# AD7685_v1.net
KiCad netlist of a schematic drawn in EAGLE
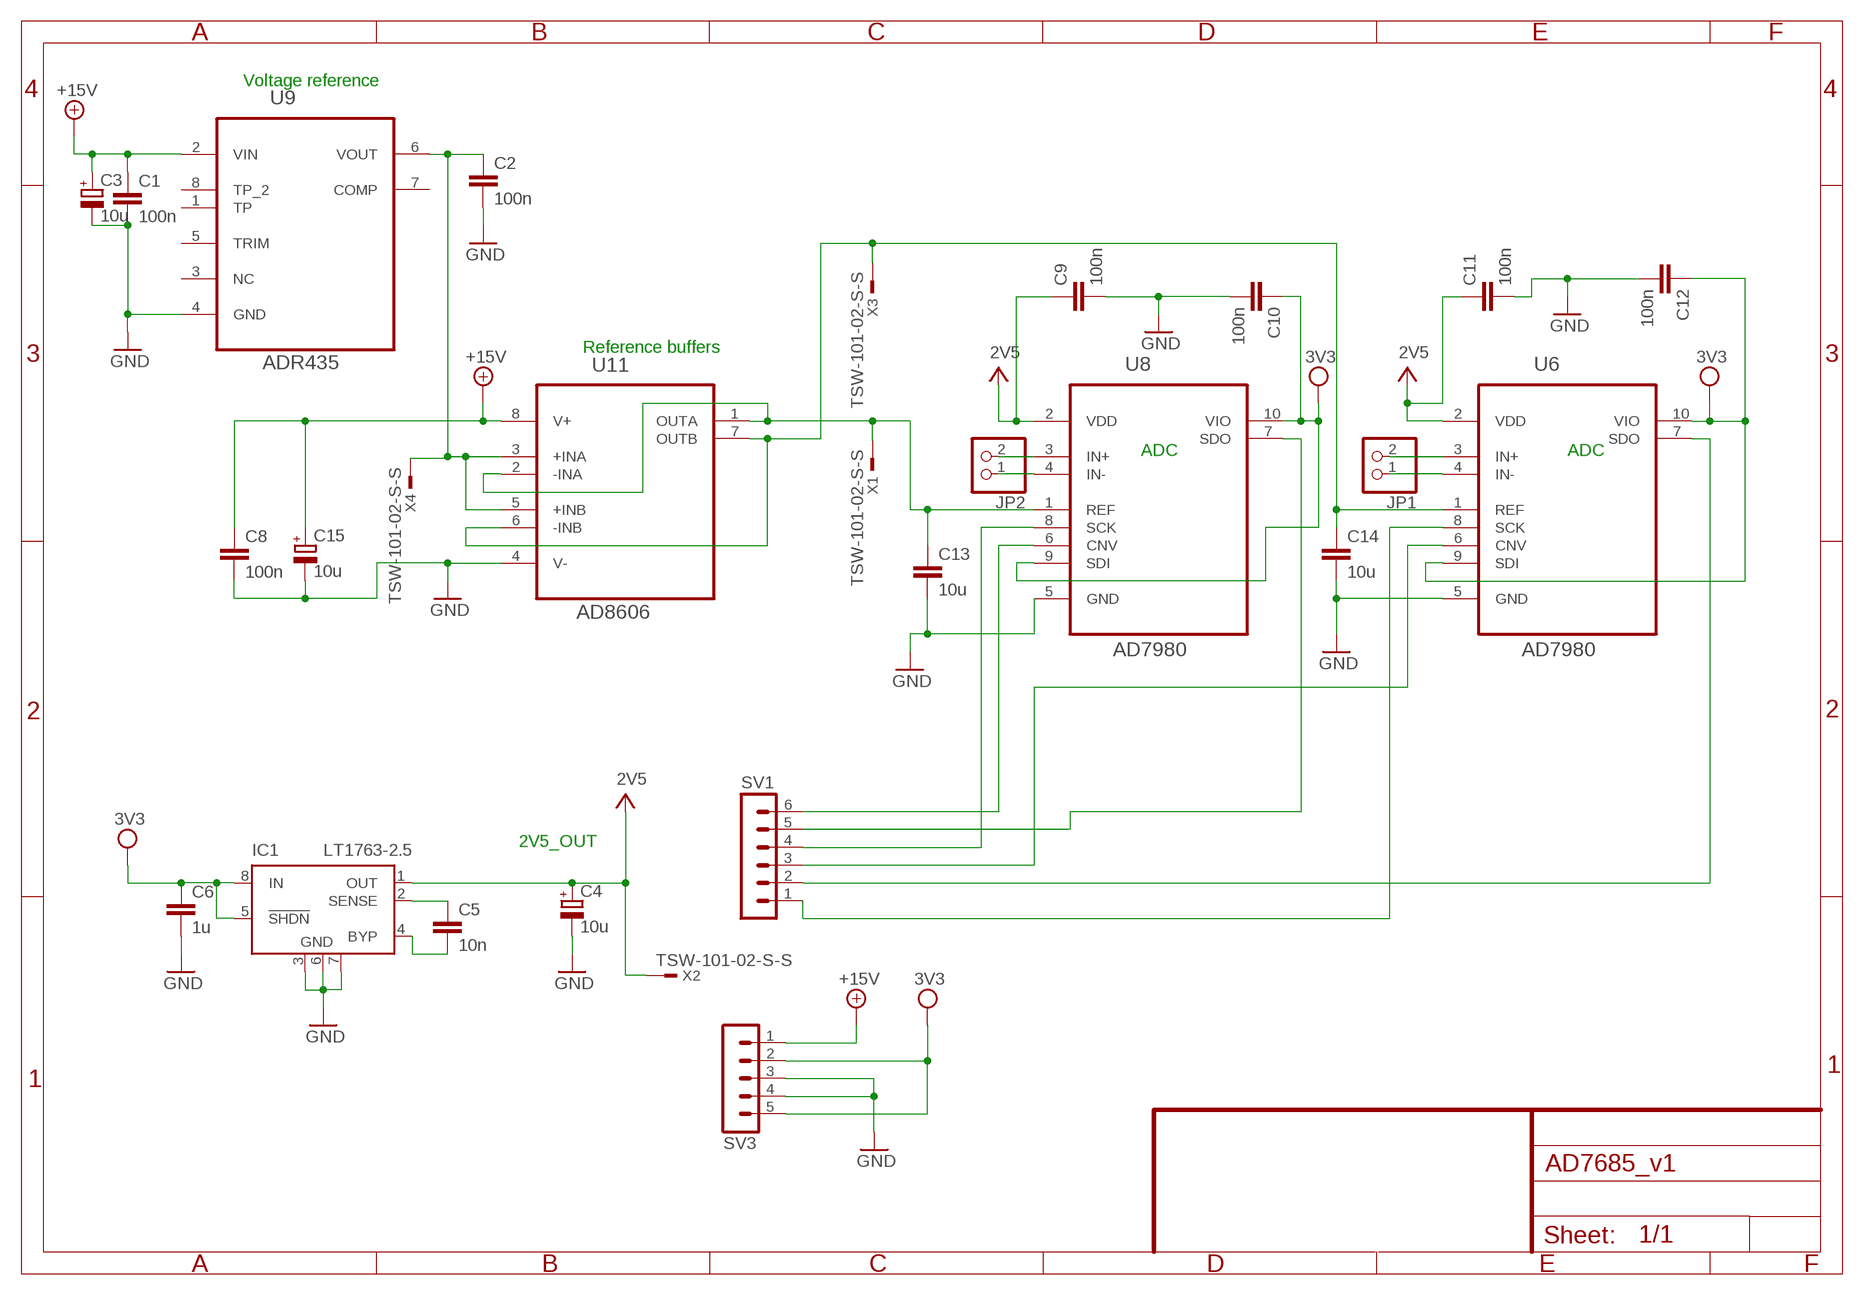
[diagram p0: schematic, sheet 1]

(export (version "E")
  (design (tool "Eeschema 10.0.6"))
  (components
    (comp (ref "C1")
      (value "100n")
      (footprint "eagle-import:C0603K")
      (libsource (lib "eagle-import") (part "C-EUC0603K"))
    )
    (comp (ref "C2")
      (value "100n")
      (footprint "eagle-import:C0603K")
      (libsource (lib "eagle-import") (part "C-EUC0603K"))
    )
    (comp (ref "C3")
      (value "10u")
      (footprint "eagle-import:SMC_A")
      (libsource (lib "eagle-import") (part "CPOL-EUSMCA"))
    )
    (comp (ref "C4")
      (value "10u")
      (footprint "eagle-import:SMC_A")
      (libsource (lib "eagle-import") (part "CPOL-EUSMCA"))
    )
    (comp (ref "C5")
      (value "10n")
      (footprint "eagle-import:C0603K")
      (libsource (lib "eagle-import") (part "C-EUC0603K"))
    )
    (comp (ref "C6")
      (value "1u")
      (footprint "eagle-import:C0603K")
      (libsource (lib "eagle-import") (part "C-EUC0603K"))
    )
    (comp (ref "C8")
      (value "100n")
      (footprint "eagle-import:C0603K")
      (libsource (lib "eagle-import") (part "C-EUC0603K"))
    )
    (comp (ref "C9")
      (value "100n")
      (footprint "eagle-import:C0603K")
      (libsource (lib "eagle-import") (part "C-EUC0603K"))
    )
    (comp (ref "C10")
      (value "100n")
      (footprint "eagle-import:C0603K")
      (libsource (lib "eagle-import") (part "C-EUC0603K"))
    )
    (comp (ref "C11")
      (value "100n")
      (footprint "eagle-import:C0603K")
      (libsource (lib "eagle-import") (part "C-EUC0603K"))
    )
    (comp (ref "C12")
      (value "100n")
      (footprint "eagle-import:C0603K")
      (libsource (lib "eagle-import") (part "C-EUC0603K"))
    )
    (comp (ref "C13")
      (value "10u")
      (footprint "eagle-import:C0603K")
      (libsource (lib "eagle-import") (part "C-EUC0603K"))
    )
    (comp (ref "C14")
      (value "10u")
      (footprint "eagle-import:C0603K")
      (libsource (lib "eagle-import") (part "C-EUC0603K"))
    )
    (comp (ref "C15")
      (value "10u")
      (footprint "eagle-import:SMC_A")
      (libsource (lib "eagle-import") (part "CPOL-EUSMCA"))
    )
    (comp (ref "IC1")
      (value "LT1763-2.5")
      (footprint "eagle-import:SOIC8")
      (fields (field (name "MPN") "LT1763CS8-2.5"))
      (libsource (lib "eagle-import") (part "LT1763CS8-2.5"))
    )
    (comp (ref "JP1")
      (value "PINHD-1X2")
      (footprint "eagle-import:1X02")
      (libsource (lib "eagle-import") (part "PINHD-1X2"))
    )
    (comp (ref "JP2")
      (value "PINHD-1X2")
      (footprint "eagle-import:1X02")
      (libsource (lib "eagle-import") (part "PINHD-1X2"))
    )
    (comp (ref "SV1")
      (value "MA06-1")
      (footprint "eagle-import:MA06-1")
      (libsource (lib "eagle-import") (part "MA06-1"))
    )
    (comp (ref "SV3")
      (value "MA05-1")
      (footprint "eagle-import:MA05-1")
      (libsource (lib "eagle-import") (part "MA05-1"))
    )
    (comp (ref "U6")
      (value "AD7980")
      (footprint "eagle-import:SOP50P490X110-10N")
      (fields (field (name "MPN") "AD7980BRMZ"))
      (libsource (lib "eagle-import") (part "AD7980BRMZ"))
    )
    (comp (ref "U8")
      (value "AD7980")
      (footprint "eagle-import:SOP50P490X110-10N")
      (fields (field (name "MPN") "AD7980BRMZ"))
      (libsource (lib "eagle-import") (part "AD7980BRMZ"))
    )
    (comp (ref "U9")
      (value "ADR435")
      (footprint "eagle-import:SOP65P490X110-8N")
      (fields (field (name "MPN") "ADR435ARMZ"))
      (libsource (lib "eagle-import") (part "ADR435ARMZ"))
    )
    (comp (ref "U11")
      (value "AD8606")
      (footprint "eagle-import:SOP65P490X110-8N")
      (fields (field (name "MPN") "AD8606ARMZ-R7"))
      (libsource (lib "eagle-import") (part "AD8606ARMZ-R7"))
    )
    (comp (ref "X1")
      (value "TSW-101-02-S-S")
      (footprint "eagle-import:TSW-101-02-S-S")
      (libsource (lib "eagle-import") (part "TSW-101-02-S-S"))
    )
    (comp (ref "X2")
      (value "TSW-101-02-S-S")
      (footprint "eagle-import:TSW-101-02-S-S")
      (libsource (lib "eagle-import") (part "TSW-101-02-S-S"))
    )
    (comp (ref "X3")
      (value "TSW-101-02-S-S")
      (footprint "eagle-import:TSW-101-02-S-S")
      (libsource (lib "eagle-import") (part "TSW-101-02-S-S"))
    )
    (comp (ref "X4")
      (value "TSW-101-02-S-S")
      (footprint "eagle-import:TSW-101-02-S-S")
      (libsource (lib "eagle-import") (part "TSW-101-02-S-S"))
    )
  )
  (nets
    (net (code "1") (name "+15V") (class "Default")
      (node (ref "C1") (pin "1") (pinfunction "1_1") (pintype "passive"))
      (node (ref "C15") (pin "+") (pinfunction "+_+") (pintype "passive"))
      (node (ref "C3") (pin "+") (pinfunction "+_+") (pintype "passive"))
      (node (ref "C8") (pin "1") (pinfunction "1_1") (pintype "passive"))
      (node (ref "SV3") (pin "1") (pinfunction "1_1") (pintype "passive"))
      (node (ref "U11") (pin "8") (pinfunction "V+_8") (pintype "power_in"))
      (node (ref "U9") (pin "2") (pinfunction "VIN_2") (pintype "power_in"))
    )
    (net (code "2") (name "/COMP") (class "Default")
      (node (ref "U9") (pin "7") (pinfunction "COMP_7") (pintype "power_in"))
    )
    (net (code "3") (name "2V5") (class "Default")
      (node (ref "C11") (pin "1") (pinfunction "1_1") (pintype "passive"))
      (node (ref "C4") (pin "+") (pinfunction "+_+") (pintype "passive"))
      (node (ref "C9") (pin "1") (pinfunction "1_1") (pintype "passive"))
      (node (ref "IC1") (pin "1") (pinfunction "OUT_1") (pintype "passive"))
      (node (ref "U6") (pin "2") (pinfunction "VDD_2") (pintype "power_in"))
      (node (ref "U8") (pin "2") (pinfunction "VDD_2") (pintype "power_in"))
      (node (ref "X2") (pin "1") (pinfunction "1_1") (pintype "passive"))
    )
    (net (code "4") (name "3V3") (class "Default")
      (node (ref "C10") (pin "1") (pinfunction "1_1") (pintype "passive"))
      (node (ref "C12") (pin "1") (pinfunction "1_1") (pintype "passive"))
      (node (ref "C6") (pin "1") (pinfunction "1_1") (pintype "passive"))
      (node (ref "IC1") (pin "5") (pinfunction "~{SHDN}_5") (pintype "input"))
      (node (ref "IC1") (pin "8") (pinfunction "IN_8") (pintype "input"))
      (node (ref "SV3") (pin "2") (pinfunction "2_2") (pintype "passive"))
      (node (ref "SV3") (pin "5") (pinfunction "5_5") (pintype "passive"))
      (node (ref "U6") (pin "10") (pinfunction "VIO_10") (pintype "bidirectional"))
      (node (ref "U6") (pin "9") (pinfunction "SDI_9") (pintype "input"))
      (node (ref "U8") (pin "10") (pinfunction "VIO_10") (pintype "bidirectional"))
      (node (ref "U8") (pin "9") (pinfunction "SDI_9") (pintype "input"))
    )
    (net (code "5") (name "GND") (class "Default")
      (node (ref "C1") (pin "2") (pinfunction "2_2") (pintype "passive"))
      (node (ref "C10") (pin "2") (pinfunction "2_2") (pintype "passive"))
      (node (ref "C11") (pin "2") (pinfunction "2_2") (pintype "passive"))
      (node (ref "C12") (pin "2") (pinfunction "2_2") (pintype "passive"))
      (node (ref "C13") (pin "2") (pinfunction "2_2") (pintype "passive"))
      (node (ref "C14") (pin "2") (pinfunction "2_2") (pintype "passive"))
      (node (ref "C15") (pin "-") (pinfunction "-_-") (pintype "passive"))
      (node (ref "C2") (pin "2") (pinfunction "2_2") (pintype "passive"))
      (node (ref "C3") (pin "-") (pinfunction "-_-") (pintype "passive"))
      (node (ref "C4") (pin "-") (pinfunction "-_-") (pintype "passive"))
      (node (ref "C6") (pin "2") (pinfunction "2_2") (pintype "passive"))
      (node (ref "C8") (pin "2") (pinfunction "2_2") (pintype "passive"))
      (node (ref "C9") (pin "2") (pinfunction "2_2") (pintype "passive"))
      (node (ref "IC1") (pin "3") (pinfunction "GND_3") (pintype "power_in"))
      (node (ref "IC1") (pin "6") (pinfunction "GND_6") (pintype "power_in"))
      (node (ref "IC1") (pin "7") (pinfunction "GND_7") (pintype "power_in"))
      (node (ref "SV3") (pin "3") (pinfunction "3_3") (pintype "passive"))
      (node (ref "SV3") (pin "4") (pinfunction "4_4") (pintype "passive"))
      (node (ref "U11") (pin "4") (pinfunction "V-_4") (pintype "power_in"))
      (node (ref "U6") (pin "5") (pinfunction "GND_5") (pintype "passive"))
      (node (ref "U8") (pin "5") (pinfunction "GND_5") (pintype "passive"))
      (node (ref "U9") (pin "4") (pinfunction "GND_4") (pintype "passive"))
    )
    (net (code "6") (name "Net-(IC1-BYP)") (class "Default")
      (node (ref "C5") (pin "2") (pinfunction "2_2") (pintype "passive"))
      (node (ref "IC1") (pin "4") (pinfunction "BYP_4") (pintype "input"))
    )
    (net (code "7") (name "Net-(IC1-SENSE)") (class "Default")
      (node (ref "C5") (pin "1") (pinfunction "1_1") (pintype "passive"))
      (node (ref "IC1") (pin "2") (pinfunction "SENSE_2") (pintype "input"))
    )
    (net (code "8") (name "Net-(U6-CNV)") (class "Default")
      (node (ref "SV1") (pin "3") (pinfunction "3_3") (pintype "passive"))
      (node (ref "U6") (pin "6") (pinfunction "CNV_6") (pintype "input"))
    )
    (net (code "9") (name "Net-(U6-IN+)") (class "Default")
      (node (ref "JP1") (pin "2") (pinfunction "2_2") (pintype "passive"))
      (node (ref "U6") (pin "3") (pinfunction "IN+_3") (pintype "input"))
    )
    (net (code "10") (name "Net-(U6-IN-)") (class "Default")
      (node (ref "JP1") (pin "1") (pinfunction "1_1") (pintype "passive"))
      (node (ref "U6") (pin "4") (pinfunction "IN-_4") (pintype "input"))
    )
    (net (code "11") (name "Net-(U6-SCK)") (class "Default")
      (node (ref "SV1") (pin "1") (pinfunction "1_1") (pintype "passive"))
      (node (ref "U6") (pin "8") (pinfunction "SCK_8") (pintype "input"))
    )
    (net (code "12") (name "Net-(U6-SDO)") (class "Default")
      (node (ref "SV1") (pin "2") (pinfunction "2_2") (pintype "passive"))
      (node (ref "U6") (pin "7") (pinfunction "SDO_7") (pintype "bidirectional"))
    )
    (net (code "13") (name "Net-(U8-CNV)") (class "Default")
      (node (ref "SV1") (pin "6") (pinfunction "6_6") (pintype "passive"))
      (node (ref "U8") (pin "6") (pinfunction "CNV_6") (pintype "input"))
    )
    (net (code "14") (name "Net-(U8-IN+)") (class "Default")
      (node (ref "JP2") (pin "2") (pinfunction "2_2") (pintype "passive"))
      (node (ref "U8") (pin "3") (pinfunction "IN+_3") (pintype "input"))
    )
    (net (code "15") (name "Net-(U8-IN-)") (class "Default")
      (node (ref "JP2") (pin "1") (pinfunction "1_1") (pintype "passive"))
      (node (ref "U8") (pin "4") (pinfunction "IN-_4") (pintype "input"))
    )
    (net (code "16") (name "Net-(U8-SCK)") (class "Default")
      (node (ref "SV1") (pin "4") (pinfunction "4_4") (pintype "passive"))
      (node (ref "U8") (pin "8") (pinfunction "SCK_8") (pintype "input"))
    )
    (net (code "17") (name "Net-(U8-SDO)") (class "Default")
      (node (ref "SV1") (pin "5") (pinfunction "5_5") (pintype "passive"))
      (node (ref "U8") (pin "7") (pinfunction "SDO_7") (pintype "bidirectional"))
    )
    (net (code "18") (name "Net-(U11-+INA)") (class "Default")
      (node (ref "C2") (pin "1") (pinfunction "1_1") (pintype "passive"))
      (node (ref "U11") (pin "3") (pinfunction "+INA_3") (pintype "input"))
      (node (ref "U11") (pin "5") (pinfunction "+INB_5") (pintype "input"))
      (node (ref "U9") (pin "6") (pinfunction "VOUT_6") (pintype "output"))
      (node (ref "X4") (pin "1") (pinfunction "1_1") (pintype "passive"))
    )
    (net (code "19") (name "Net-(U11--INA)") (class "Default")
      (node (ref "C13") (pin "1") (pinfunction "1_1") (pintype "passive"))
      (node (ref "U11") (pin "1") (pinfunction "OUTA_1") (pintype "output"))
      (node (ref "U11") (pin "2") (pinfunction "-INA_2") (pintype "input"))
      (node (ref "U8") (pin "1") (pinfunction "REF_1") (pintype "input"))
      (node (ref "X1") (pin "1") (pinfunction "1_1") (pintype "passive"))
    )
    (net (code "20") (name "Net-(U11--INB)") (class "Default")
      (node (ref "C14") (pin "1") (pinfunction "1_1") (pintype "passive"))
      (node (ref "U11") (pin "6") (pinfunction "-INB_6") (pintype "input"))
      (node (ref "U11") (pin "7") (pinfunction "OUTB_7") (pintype "output"))
      (node (ref "U6") (pin "1") (pinfunction "REF_1") (pintype "input"))
      (node (ref "X3") (pin "1") (pinfunction "1_1") (pintype "passive"))
    )
    (net (code "21") (name "unconnected-(U9-NC-Pad3)") (class "Default")
      (node (ref "U9") (pin "3") (pinfunction "NC_3") (pintype "no_connect"))
    )
    (net (code "22") (name "unconnected-(U9-TP-Pad1)") (class "Default")
      (node (ref "U9") (pin "1") (pinfunction "TP_1") (pintype "passive"))
    )
    (net (code "23") (name "unconnected-(U9-TP_2-Pad8)") (class "Default")
      (node (ref "U9") (pin "8") (pinfunction "TP_2_8") (pintype "passive"))
    )
    (net (code "24") (name "unconnected-(U9-TRIM-Pad5)") (class "Default")
      (node (ref "U9") (pin "5") (pinfunction "TRIM_5") (pintype "passive"))
    )
  )
)
